# eeZee_big_tiny.net
KiCad netlist of a schematic drawn in EAGLE
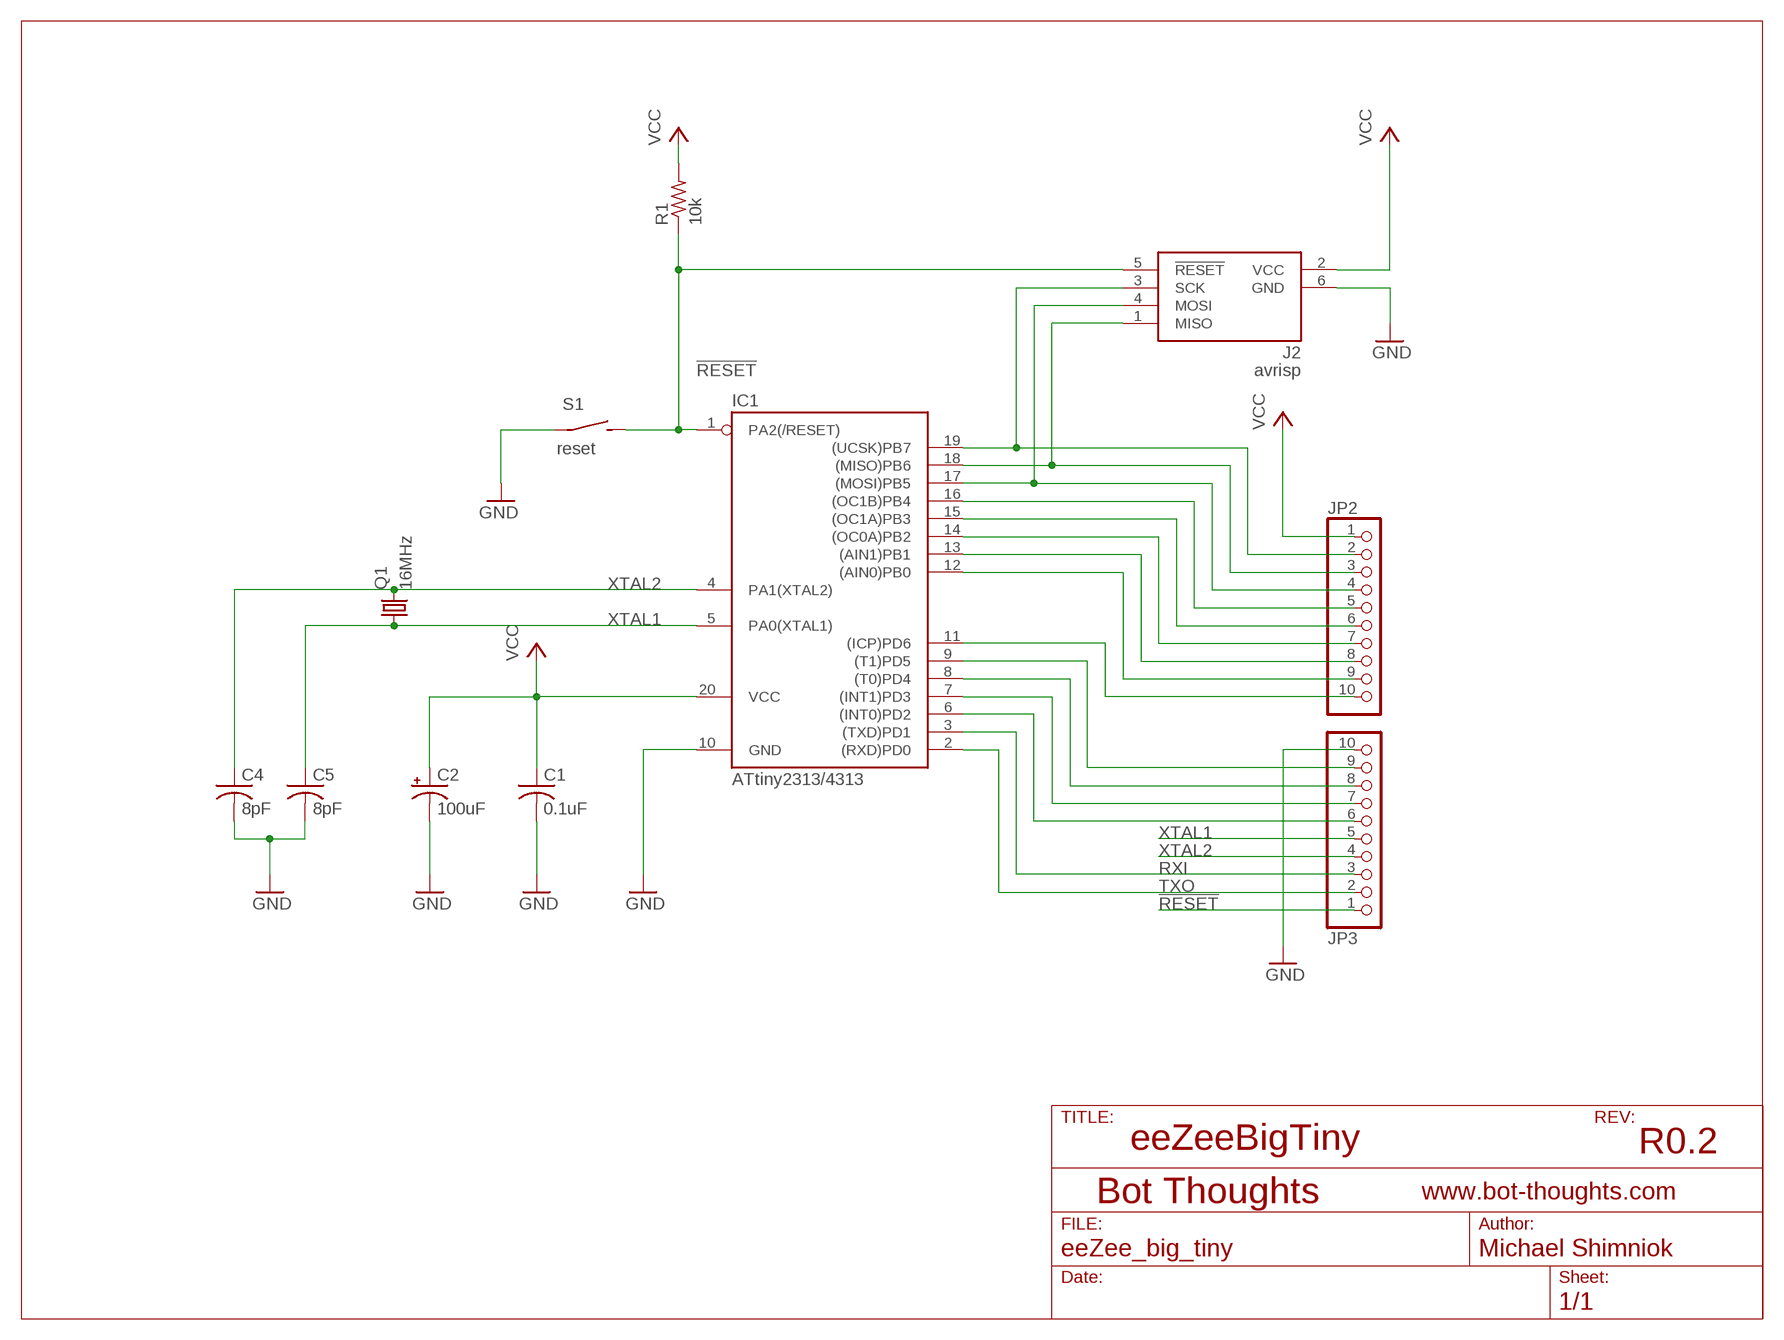
[diagram p0: schematic, sheet 1]

(export (version "E")
  (design (tool "Eeschema 10.0.6"))
  (components
    (comp (ref "C1")
      (value "0.1uF")
      (footprint "eagle-import:C0603")
      (fields (field (name "PARTNO") "0603YC104KAT2A"))
      (libsource (lib "eagle-import") (part "C-USC0603"))
    )
    (comp (ref "C2")
      (value "100uF")
      (footprint "eagle-import:SMC_B")
      (fields (field (name "PARTNO") "MCTT21X106M6R3CT"))
      (libsource (lib "eagle-import") (part "CAP_POL_SMC_B"))
    )
    (comp (ref "C4")
      (value "8pF")
      (footprint "eagle-import:C0603")
      (fields (field (name "PARTNO") "0603YC104KAT2A"))
      (libsource (lib "eagle-import") (part "C-USC0603"))
    )
    (comp (ref "C5")
      (value "8pF")
      (footprint "eagle-import:C0603")
      (fields (field (name "PARTNO") "0603YC104KAT2A"))
      (libsource (lib "eagle-import") (part "C-USC0603"))
    )
    (comp (ref "IC1")
      (value "ATtiny2313/4313")
      (footprint "eagle-import:DIL20")
      (libsource (lib "eagle-import") (part "TINY2313-P"))
    )
    (comp (ref "J2")
      (value "avrisp")
      (footprint "eagle-import:CON6P2R")
      (libsource (lib "eagle-import") (part "AVRISP6"))
    )
    (comp (ref "JP2")
      (value "PINHD-1X10_2.54-S")
      (footprint "eagle-import:1X10-S")
      (libsource (lib "eagle-import") (part "PINHD-1X10_2.54-S"))
    )
    (comp (ref "JP3")
      (value "PINHD-1X10_2.54-S")
      (footprint "eagle-import:1X10-S")
      (libsource (lib "eagle-import") (part "PINHD-1X10_2.54-S"))
    )
    (comp (ref "Q1")
      (value "16MHz")
      (footprint "eagle-import:NDK_2PAD_5X3")
      (libsource (lib "eagle-import") (part "CRYSTALNDK5X3"))
    )
    (comp (ref "R1")
      (value "10k")
      (footprint "eagle-import:R0603")
      (fields (field (name "PARTNO") "ERJ-3GEYJ103V"))
      (libsource (lib "eagle-import") (part "R-US_R0603"))
    )
    (comp (ref "S1")
      (value "reset")
      (footprint "eagle-import:6MMTACTILE_RECT")
      (libsource (lib "eagle-import") (part "SPST_TAC_RECT1"))
    )
  )
  (nets
    (net (code "1") (name "/RXI") (class "Default")
      (node (ref "IC1") (pin "3") (pinfunction "(TXD)PD1_3") (pintype "bidirectional"))
      (node (ref "JP3") (pin "3") (pinfunction "3_3") (pintype "passive"))
    )
    (net (code "2") (name "/TXO") (class "Default")
      (node (ref "IC1") (pin "2") (pinfunction "(RXD)PD0_2") (pintype "bidirectional"))
      (node (ref "JP3") (pin "2") (pinfunction "2_2") (pintype "passive"))
    )
    (net (code "3") (name "/XTAL1") (class "Default")
      (node (ref "C5") (pin "1") (pinfunction "1_1") (pintype "passive"))
      (node (ref "IC1") (pin "5") (pinfunction "PA0(XTAL1)_5") (pintype "bidirectional"))
      (node (ref "JP3") (pin "5") (pinfunction "5_5") (pintype "passive"))
      (node (ref "Q1") (pin "P$1") (pinfunction "1_P$1") (pintype "passive"))
    )
    (net (code "4") (name "/XTAL2") (class "Default")
      (node (ref "C4") (pin "1") (pinfunction "1_1") (pintype "passive"))
      (node (ref "IC1") (pin "4") (pinfunction "PA1(XTAL2)_4") (pintype "bidirectional"))
      (node (ref "JP3") (pin "4") (pinfunction "4_4") (pintype "passive"))
      (node (ref "Q1") (pin "P$2") (pinfunction "2_P$2") (pintype "passive"))
    )
    (net (code "5") (name "/~{RESET}") (class "Default")
      (node (ref "IC1") (pin "1") (pinfunction "PA2(/RESET)_1") (pintype "input"))
      (node (ref "J2") (pin "5") (pinfunction "~{RESET}_5") (pintype "output"))
      (node (ref "JP3") (pin "1") (pinfunction "1_1") (pintype "passive"))
      (node (ref "R1") (pin "1") (pinfunction "1_1") (pintype "passive"))
      (node (ref "S1") (pin "P$2") (pinfunction "S_P$2") (pintype "passive"))
    )
    (net (code "6") (name "GND") (class "Default")
      (node (ref "C1") (pin "2") (pinfunction "2_2") (pintype "passive"))
      (node (ref "C2") (pin "-") (pinfunction "-_-") (pintype "passive"))
      (node (ref "C4") (pin "2") (pinfunction "2_2") (pintype "passive"))
      (node (ref "C5") (pin "2") (pinfunction "2_2") (pintype "passive"))
      (node (ref "IC1") (pin "10") (pinfunction "GND_10") (pintype "power_in"))
      (node (ref "J2") (pin "6") (pinfunction "GND_6") (pintype "power_in"))
      (node (ref "JP3") (pin "10") (pinfunction "10_10") (pintype "passive"))
      (node (ref "S1") (pin "P$1") (pinfunction "P_P$1") (pintype "passive"))
    )
    (net (code "7") (name "Net-(IC1-(AIN0)PB0)") (class "Default")
      (node (ref "IC1") (pin "12") (pinfunction "(AIN0)PB0_12") (pintype "bidirectional"))
      (node (ref "JP2") (pin "9") (pinfunction "9_9") (pintype "passive"))
    )
    (net (code "8") (name "Net-(IC1-(AIN1)PB1)") (class "Default")
      (node (ref "IC1") (pin "13") (pinfunction "(AIN1)PB1_13") (pintype "bidirectional"))
      (node (ref "JP2") (pin "8") (pinfunction "8_8") (pintype "passive"))
    )
    (net (code "9") (name "Net-(IC1-(ICP)PD6)") (class "Default")
      (node (ref "IC1") (pin "11") (pinfunction "(ICP)PD6_11") (pintype "bidirectional"))
      (node (ref "JP2") (pin "10") (pinfunction "10_10") (pintype "passive"))
    )
    (net (code "10") (name "Net-(IC1-(INT0)PD2)") (class "Default")
      (node (ref "IC1") (pin "6") (pinfunction "(INT0)PD2_6") (pintype "bidirectional"))
      (node (ref "JP3") (pin "6") (pinfunction "6_6") (pintype "passive"))
    )
    (net (code "11") (name "Net-(IC1-(INT1)PD3)") (class "Default")
      (node (ref "IC1") (pin "7") (pinfunction "(INT1)PD3_7") (pintype "bidirectional"))
      (node (ref "JP3") (pin "7") (pinfunction "7_7") (pintype "passive"))
    )
    (net (code "12") (name "Net-(IC1-(MISO)PB6)") (class "Default")
      (node (ref "IC1") (pin "18") (pinfunction "(MISO)PB6_18") (pintype "bidirectional"))
      (node (ref "J2") (pin "1") (pinfunction "MISO_1") (pintype "input"))
      (node (ref "JP2") (pin "3") (pinfunction "3_3") (pintype "passive"))
    )
    (net (code "13") (name "Net-(IC1-(MOSI)PB5)") (class "Default")
      (node (ref "IC1") (pin "17") (pinfunction "(MOSI)PB5_17") (pintype "bidirectional"))
      (node (ref "J2") (pin "4") (pinfunction "MOSI_4") (pintype "output"))
      (node (ref "JP2") (pin "4") (pinfunction "4_4") (pintype "passive"))
    )
    (net (code "14") (name "Net-(IC1-(OC0A)PB2)") (class "Default")
      (node (ref "IC1") (pin "14") (pinfunction "(OC0A)PB2_14") (pintype "bidirectional"))
      (node (ref "JP2") (pin "7") (pinfunction "7_7") (pintype "passive"))
    )
    (net (code "15") (name "Net-(IC1-(OC1A)PB3)") (class "Default")
      (node (ref "IC1") (pin "15") (pinfunction "(OC1A)PB3_15") (pintype "bidirectional"))
      (node (ref "JP2") (pin "6") (pinfunction "6_6") (pintype "passive"))
    )
    (net (code "16") (name "Net-(IC1-(OC1B)PB4)") (class "Default")
      (node (ref "IC1") (pin "16") (pinfunction "(OC1B)PB4_16") (pintype "bidirectional"))
      (node (ref "JP2") (pin "5") (pinfunction "5_5") (pintype "passive"))
    )
    (net (code "17") (name "Net-(IC1-(T0)PD4)") (class "Default")
      (node (ref "IC1") (pin "8") (pinfunction "(T0)PD4_8") (pintype "bidirectional"))
      (node (ref "JP3") (pin "8") (pinfunction "8_8") (pintype "passive"))
    )
    (net (code "18") (name "Net-(IC1-(T1)PD5)") (class "Default")
      (node (ref "IC1") (pin "9") (pinfunction "(T1)PD5_9") (pintype "bidirectional"))
      (node (ref "JP3") (pin "9") (pinfunction "9_9") (pintype "passive"))
    )
    (net (code "19") (name "Net-(IC1-(UCSK)PB7)") (class "Default")
      (node (ref "IC1") (pin "19") (pinfunction "(UCSK)PB7_19") (pintype "bidirectional"))
      (node (ref "J2") (pin "3") (pinfunction "SCK_3") (pintype "output"))
      (node (ref "JP2") (pin "2") (pinfunction "2_2") (pintype "passive"))
    )
    (net (code "20") (name "VCC") (class "Default")
      (node (ref "C1") (pin "1") (pinfunction "1_1") (pintype "passive"))
      (node (ref "C2") (pin "+") (pinfunction "+_+") (pintype "passive"))
      (node (ref "IC1") (pin "20") (pinfunction "VCC_20") (pintype "power_in"))
      (node (ref "J2") (pin "2") (pinfunction "VCC_2") (pintype "power_in"))
      (node (ref "JP2") (pin "1") (pinfunction "1_1") (pintype "passive"))
      (node (ref "R1") (pin "2") (pinfunction "2_2") (pintype "passive"))
    )
  )
)
